# supply.net
KiCad netlist of a schematic drawn in EAGLE
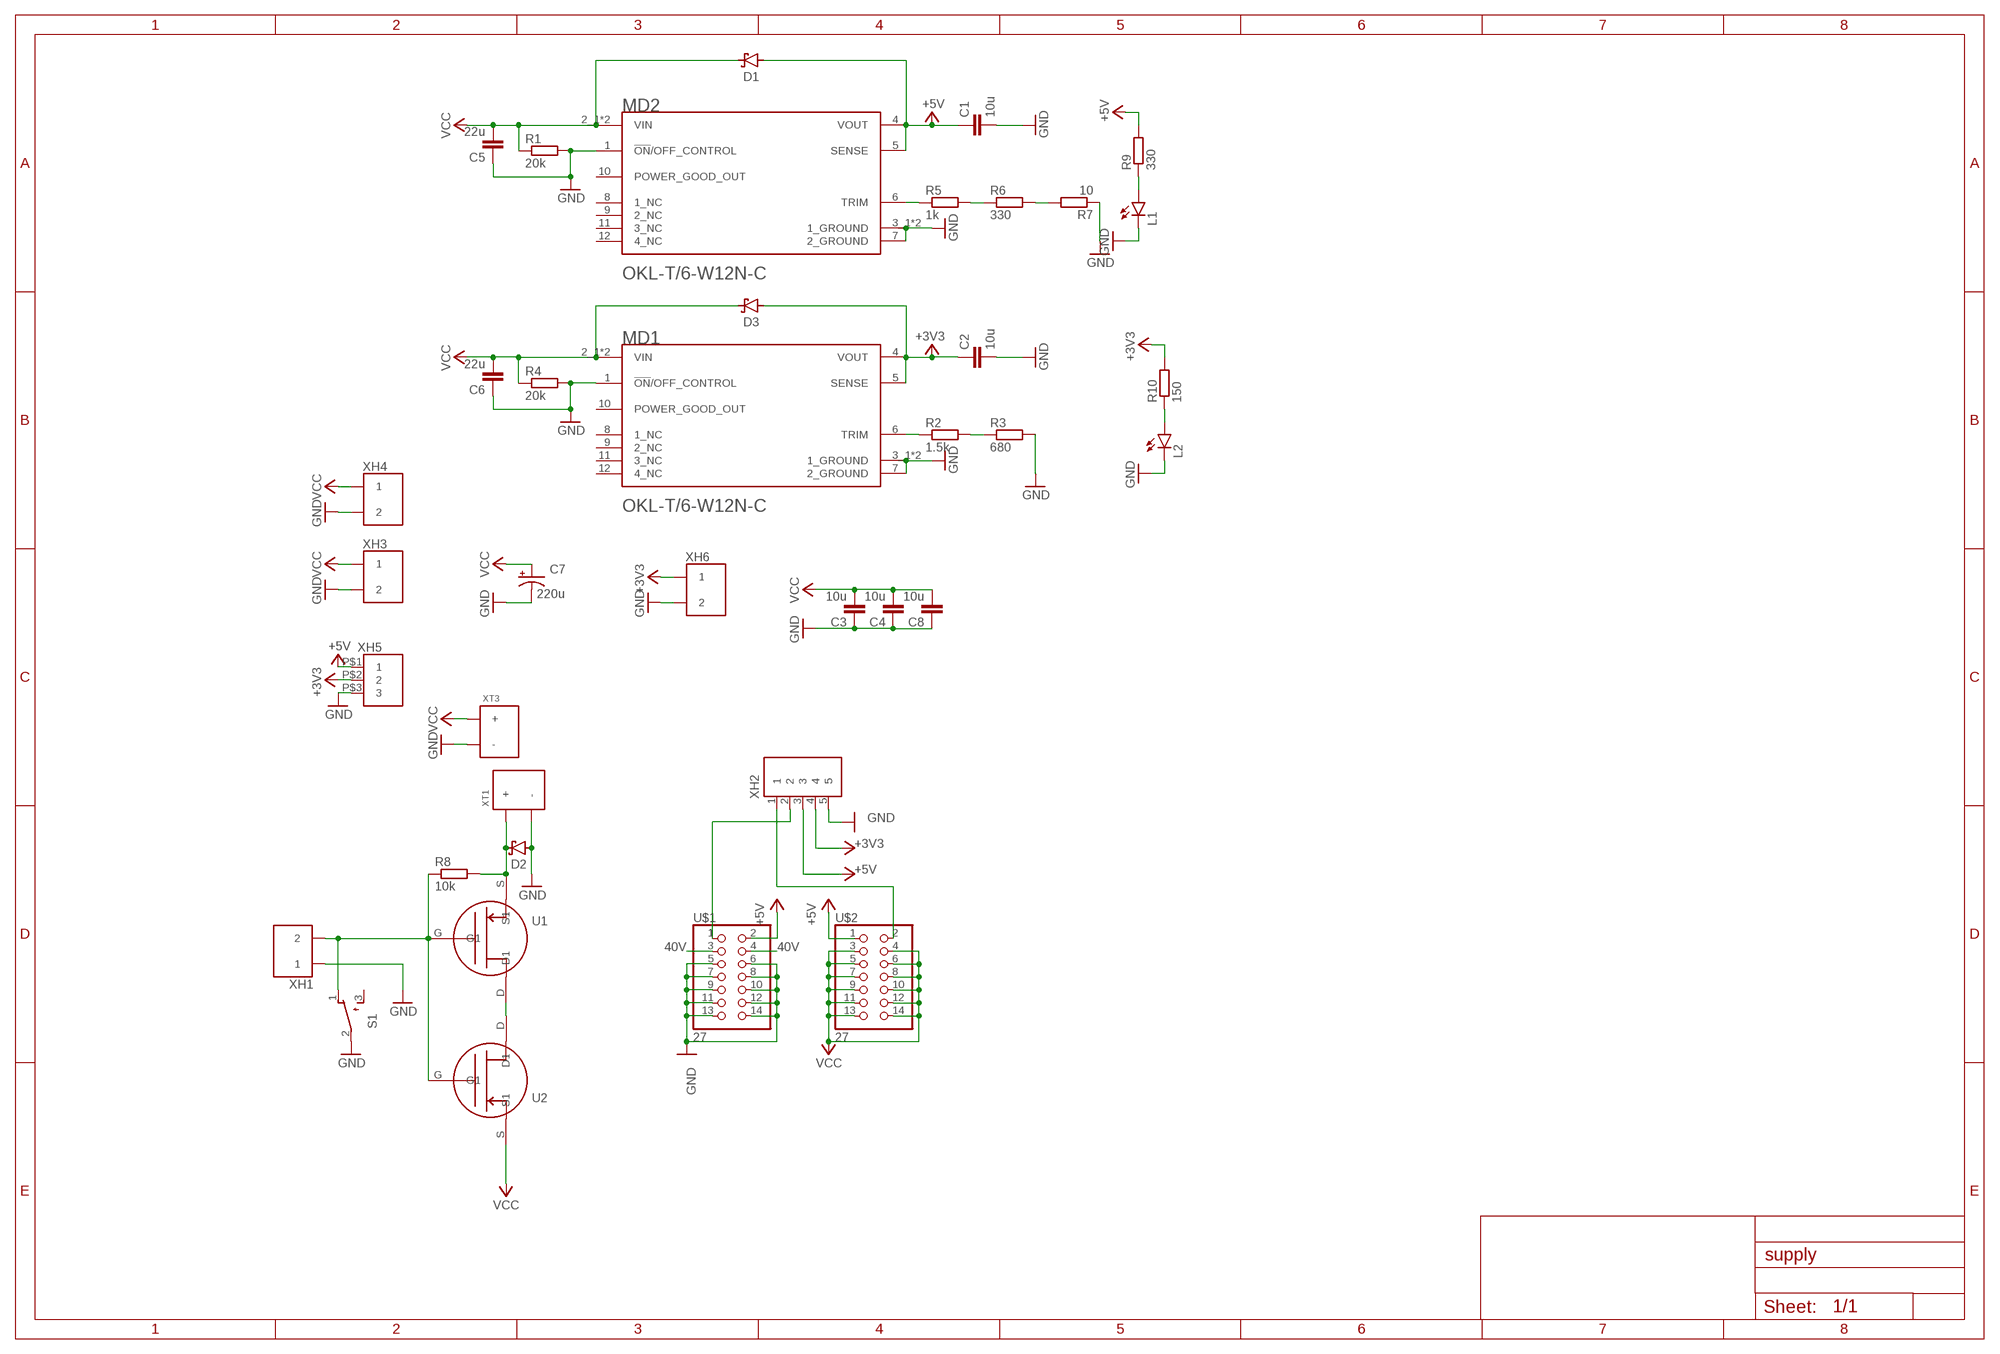
[diagram p0: schematic, sheet 1]

(export (version "E")
  (design (tool "Eeschema 10.0.6"))
  (components
    (comp (ref "C1")
      (value "10u")
      (footprint "eagle-import:C0805")
      (libsource (lib "eagle-import") (part "C-EUC0805"))
    )
    (comp (ref "C2")
      (value "10u")
      (footprint "eagle-import:C0805")
      (libsource (lib "eagle-import") (part "C-EUC0805"))
    )
    (comp (ref "C3")
      (value "10u")
      (footprint "eagle-import:C0805")
      (libsource (lib "eagle-import") (part "C-EUC0805"))
    )
    (comp (ref "C4")
      (value "10u")
      (footprint "eagle-import:C0805")
      (libsource (lib "eagle-import") (part "C-EUC0805"))
    )
    (comp (ref "C5")
      (value "22u")
      (footprint "eagle-import:C0805")
      (libsource (lib "eagle-import") (part "C-EUC0805"))
    )
    (comp (ref "C6")
      (value "22u")
      (footprint "eagle-import:C0805")
      (libsource (lib "eagle-import") (part "C-EUC0805"))
    )
    (comp (ref "C7")
      (value "220u")
      (footprint "eagle-import:CAPAE830X1080N")
      (libsource (lib "eagle-import") (part "UWT1E221MNL1GS"))
    )
    (comp (ref "C8")
      (value "10u")
      (footprint "eagle-import:C0805")
      (libsource (lib "eagle-import") (part "C-EUC0805"))
    )
    (comp (ref "D1")
      (value "SS2040FL")
      (footprint "eagle-import:SOD123FL")
      (libsource (lib "eagle-import") (part "SS2040FL"))
    )
    (comp (ref "D2")
      (value "SS2040FL")
      (footprint "eagle-import:SOD123FL")
      (libsource (lib "eagle-import") (part "SS2040FL"))
    )
    (comp (ref "D3")
      (value "SS2040FL")
      (footprint "eagle-import:SOD123FL")
      (libsource (lib "eagle-import") (part "SS2040FL"))
    )
    (comp (ref "L1")
      (value "SML-E12P8WT86")
      (footprint "eagle-import:LED_SML-LXFM0603SIC-TR")
      (libsource (lib "eagle-import") (part "SML-E12P8WT86"))
    )
    (comp (ref "L2")
      (value "SML-E12P8WT86")
      (footprint "eagle-import:LED_SML-LXFM0603SIC-TR")
      (libsource (lib "eagle-import") (part "SML-E12P8WT86"))
    )
    (comp (ref "MD1")
      (value "OKL-T/6-W12N-CMURATA_OKL-T-6-W12N-C_0_0")
      (footprint "eagle-import:MURATA_OKL-T-6-W12N-C_0")
      (fields (field (name "MF") "Murata Power Solutions Inc.") (field (name "MP") "OKL-T/6-W12N-C"))
      (libsource (lib "eagle-import") (part "OKL-T/6-W12N-CMURATA_OKL-T-6-W12N-C_0_0"))
    )
    (comp (ref "MD2")
      (value "OKL-T/6-W12N-CMURATA_OKL-T-6-W12N-C_0_0")
      (footprint "eagle-import:MURATA_OKL-T-6-W12N-C_0")
      (fields (field (name "MF") "Murata Power Solutions Inc.") (field (name "MP") "OKL-T/6-W12N-C"))
      (libsource (lib "eagle-import") (part "OKL-T/6-W12N-CMURATA_OKL-T-6-W12N-C_0_0"))
    )
    (comp (ref "R1")
      (value "20k")
      (footprint "eagle-import:R0603")
      (libsource (lib "eagle-import") (part "R-EU_R0603"))
    )
    (comp (ref "R2")
      (value "1.5k")
      (footprint "eagle-import:R0603")
      (libsource (lib "eagle-import") (part "R-EU_R0603"))
    )
    (comp (ref "R3")
      (value "680")
      (footprint "eagle-import:R0603")
      (libsource (lib "eagle-import") (part "R-EU_R0603"))
    )
    (comp (ref "R4")
      (value "20k")
      (footprint "eagle-import:R0603")
      (libsource (lib "eagle-import") (part "R-EU_R0603"))
    )
    (comp (ref "R5")
      (value "1k")
      (footprint "eagle-import:R0603")
      (libsource (lib "eagle-import") (part "R-EU_R0603"))
    )
    (comp (ref "R6")
      (value "330")
      (footprint "eagle-import:R0603")
      (libsource (lib "eagle-import") (part "R-EU_R0603"))
    )
    (comp (ref "R7")
      (value "10")
      (footprint "eagle-import:R0603")
      (libsource (lib "eagle-import") (part "R-EU_R0603"))
    )
    (comp (ref "R8")
      (value "10k")
      (footprint "eagle-import:R0603")
      (libsource (lib "eagle-import") (part "R-EU_R0603"))
    )
    (comp (ref "R9")
      (value "330")
      (footprint "eagle-import:R0603")
      (libsource (lib "eagle-import") (part "R-EU_R0603"))
    )
    (comp (ref "R10")
      (value "150")
      (footprint "eagle-import:R0603")
      (libsource (lib "eagle-import") (part "R-EU_R0603"))
    )
    (comp (ref "S1")
      (value "SS-12SDP2")
      (footprint "eagle-import:SS-12SDP2")
      (libsource (lib "eagle-import") (part "SS-12SDP2"))
    )
    (comp (ref "U$1")
      (value "27")
      (footprint "eagle-import:2_7")
      (libsource (lib "eagle-import") (part "27"))
    )
    (comp (ref "U$2")
      (value "27")
      (footprint "eagle-import:2_7")
      (libsource (lib "eagle-import") (part "27"))
    )
    (comp (ref "U1")
      (value "TJ60S04M3L")
      (footprint "eagle-import:DPACK")
      (libsource (lib "eagle-import") (part "TJ60S04M3L"))
    )
    (comp (ref "U2")
      (value "TJ60S04M3L")
      (footprint "eagle-import:DPACK")
      (libsource (lib "eagle-import") (part "TJ60S04M3L"))
    )
    (comp (ref "XH1") (value "2B") (footprint "eagle-import:2B") (libsource (lib "eagle-import") (part "2B")))
    (comp (ref "XH2") (value "5B") (footprint "eagle-import:5B") (libsource (lib "eagle-import") (part "5B")))
    (comp (ref "XH3") (value "2B") (footprint "eagle-import:2B") (libsource (lib "eagle-import") (part "2B")))
    (comp (ref "XH4") (value "2B") (footprint "eagle-import:2B") (libsource (lib "eagle-import") (part "2B")))
    (comp (ref "XH5") (value "3B") (footprint "eagle-import:3B") (libsource (lib "eagle-import") (part "3B")))
    (comp (ref "XH6") (value "2B") (footprint "eagle-import:2B") (libsource (lib "eagle-import") (part "2B")))
    (comp (ref "XT1")
      (value "XT60U-M")
      (footprint "eagle-import:XT60U-M")
      (libsource (lib "eagle-import") (part "XT60U-M"))
    )
    (comp (ref "XT3")
      (value "XT30U-M")
      (footprint "eagle-import:XT30U-M")
      (libsource (lib "eagle-import") (part "XT30U-M"))
    )
  )
  (nets
    (net (code "1") (name "+3V3") (class "Default")
      (node (ref "C2") (pin "1") (pinfunction "1_1") (pintype "passive"))
      (node (ref "D3") (pin "A") (pinfunction "A_A") (pintype "passive"))
      (node (ref "MD1") (pin "4") (pinfunction "VOUT_4") (pintype "bidirectional"))
      (node (ref "MD1") (pin "5") (pinfunction "SENSE_5") (pintype "passive"))
      (node (ref "R10") (pin "2") (pinfunction "2_2") (pintype "passive"))
      (node (ref "XH2") (pin "4") (pinfunction "4_4") (pintype "bidirectional"))
      (node (ref "XH5") (pin "P$2") (pinfunction "2_P$2") (pintype "bidirectional"))
      (node (ref "XH6") (pin "P$1") (pinfunction "1_P$1") (pintype "bidirectional"))
    )
    (net (code "2") (name "+5V") (class "Default")
      (node (ref "C1") (pin "1") (pinfunction "1_1") (pintype "passive"))
      (node (ref "D1") (pin "A") (pinfunction "A_A") (pintype "passive"))
      (node (ref "MD2") (pin "4") (pinfunction "VOUT_4") (pintype "bidirectional"))
      (node (ref "MD2") (pin "5") (pinfunction "SENSE_5") (pintype "passive"))
      (node (ref "R9") (pin "2") (pinfunction "2_2") (pintype "passive"))
      (node (ref "U$1") (pin "2") (pinfunction "2_2") (pintype "passive"))
      (node (ref "U$2") (pin "1") (pinfunction "1_1") (pintype "passive"))
      (node (ref "XH2") (pin "3") (pinfunction "3_3") (pintype "bidirectional"))
      (node (ref "XH5") (pin "P$1") (pinfunction "1_P$1") (pintype "bidirectional"))
    )
    (net (code "3") (name "/40V") (class "Default")
      (node (ref "U$1") (pin "3") (pinfunction "3_3") (pintype "passive"))
      (node (ref "U$1") (pin "4") (pinfunction "4_4") (pintype "passive"))
    )
    (net (code "4") (name "GND") (class "Default")
      (node (ref "C1") (pin "2") (pinfunction "2_2") (pintype "passive"))
      (node (ref "C2") (pin "2") (pinfunction "2_2") (pintype "passive"))
      (node (ref "C3") (pin "1") (pinfunction "1_1") (pintype "passive"))
      (node (ref "C4") (pin "1") (pinfunction "1_1") (pintype "passive"))
      (node (ref "C5") (pin "1") (pinfunction "1_1") (pintype "passive"))
      (node (ref "C6") (pin "1") (pinfunction "1_1") (pintype "passive"))
      (node (ref "C7") (pin "-") (pinfunction "-_-") (pintype "passive"))
      (node (ref "C8") (pin "1") (pinfunction "1_1") (pintype "passive"))
      (node (ref "D2") (pin "A") (pinfunction "A_A") (pintype "passive"))
      (node (ref "L1") (pin "C") (pinfunction "C_C") (pintype "passive"))
      (node (ref "L2") (pin "C") (pinfunction "C_C") (pintype "passive"))
      (node (ref "MD1") (pin "1") (pinfunction "~{ON}/OFF_CONTROL_1") (pintype "bidirectional"))
      (node (ref "MD1") (pin "3_1") (pinfunction "1_GROUND_3_1") (pintype "power_in"))
      (node (ref "MD1") (pin "3_2") (pinfunction "1_GROUND_3_2") (pintype "power_in"))
      (node (ref "MD1") (pin "7") (pinfunction "2_GROUND_7") (pintype "power_in"))
      (node (ref "MD2") (pin "1") (pinfunction "~{ON}/OFF_CONTROL_1") (pintype "bidirectional"))
      (node (ref "MD2") (pin "3_1") (pinfunction "1_GROUND_3_1") (pintype "power_in"))
      (node (ref "MD2") (pin "3_2") (pinfunction "1_GROUND_3_2") (pintype "power_in"))
      (node (ref "MD2") (pin "7") (pinfunction "2_GROUND_7") (pintype "power_in"))
      (node (ref "R1") (pin "2") (pinfunction "2_2") (pintype "passive"))
      (node (ref "R3") (pin "2") (pinfunction "2_2") (pintype "passive"))
      (node (ref "R4") (pin "2") (pinfunction "2_2") (pintype "passive"))
      (node (ref "R7") (pin "1") (pinfunction "1_1") (pintype "passive"))
      (node (ref "S1") (pin "2") (pinfunction "2_2") (pintype "passive"))
      (node (ref "U$1") (pin "10") (pinfunction "10_10") (pintype "passive"))
      (node (ref "U$1") (pin "11") (pinfunction "11_11") (pintype "passive"))
      (node (ref "U$1") (pin "12") (pinfunction "12_12") (pintype "passive"))
      (node (ref "U$1") (pin "13") (pinfunction "13_13") (pintype "passive"))
      (node (ref "U$1") (pin "14") (pinfunction "14_14") (pintype "passive"))
      (node (ref "U$1") (pin "5") (pinfunction "5_5") (pintype "passive"))
      (node (ref "U$1") (pin "6") (pinfunction "6_6") (pintype "passive"))
      (node (ref "U$1") (pin "7") (pinfunction "7_7") (pintype "passive"))
      (node (ref "U$1") (pin "8") (pinfunction "8_8") (pintype "passive"))
      (node (ref "U$1") (pin "9") (pinfunction "9_9") (pintype "passive"))
      (node (ref "XH1") (pin "P$1") (pinfunction "1_P$1") (pintype "bidirectional"))
      (node (ref "XH2") (pin "5") (pinfunction "5_5") (pintype "bidirectional"))
      (node (ref "XH3") (pin "P$2") (pinfunction "2_P$2") (pintype "bidirectional"))
      (node (ref "XH4") (pin "P$2") (pinfunction "2_P$2") (pintype "bidirectional"))
      (node (ref "XH5") (pin "P$3") (pinfunction "3_P$3") (pintype "bidirectional"))
      (node (ref "XH6") (pin "P$2") (pinfunction "2_P$2") (pintype "bidirectional"))
      (node (ref "XT1") (pin "-") (pinfunction "-_-") (pintype "bidirectional"))
      (node (ref "XT3") (pin "-") (pinfunction "-_-") (pintype "bidirectional"))
    )
    (net (code "5") (name "Net-(L1-PadA)") (class "Default")
      (node (ref "L1") (pin "A") (pinfunction "A_A") (pintype "passive"))
      (node (ref "R9") (pin "1") (pinfunction "1_1") (pintype "passive"))
    )
    (net (code "6") (name "Net-(L2-PadA)") (class "Default")
      (node (ref "L2") (pin "A") (pinfunction "A_A") (pintype "passive"))
      (node (ref "R10") (pin "1") (pinfunction "1_1") (pintype "passive"))
    )
    (net (code "7") (name "Net-(MD1-TRIM)") (class "Default")
      (node (ref "MD1") (pin "6") (pinfunction "TRIM_6") (pintype "passive"))
      (node (ref "R2") (pin "1") (pinfunction "1_1") (pintype "passive"))
    )
    (net (code "8") (name "Net-(MD2-TRIM)") (class "Default")
      (node (ref "MD2") (pin "6") (pinfunction "TRIM_6") (pintype "passive"))
      (node (ref "R5") (pin "1") (pinfunction "1_1") (pintype "passive"))
    )
    (net (code "9") (name "Net-(R2-Pad2)") (class "Default")
      (node (ref "R2") (pin "2") (pinfunction "2_2") (pintype "passive"))
      (node (ref "R3") (pin "1") (pinfunction "1_1") (pintype "passive"))
    )
    (net (code "10") (name "Net-(R5-Pad2)") (class "Default")
      (node (ref "R5") (pin "2") (pinfunction "2_2") (pintype "passive"))
      (node (ref "R6") (pin "1") (pinfunction "1_1") (pintype "passive"))
    )
    (net (code "11") (name "Net-(R6-Pad2)") (class "Default")
      (node (ref "R6") (pin "2") (pinfunction "2_2") (pintype "passive"))
      (node (ref "R7") (pin "2") (pinfunction "2_2") (pintype "passive"))
    )
    (net (code "12") (name "Net-(U$1-Pad1)") (class "Default")
      (node (ref "U$1") (pin "1") (pinfunction "1_1") (pintype "passive"))
      (node (ref "XH2") (pin "2") (pinfunction "2_2") (pintype "bidirectional"))
    )
    (net (code "13") (name "Net-(U$2-Pad2)") (class "Default")
      (node (ref "U$2") (pin "2") (pinfunction "2_2") (pintype "passive"))
      (node (ref "XH2") (pin "1") (pinfunction "1_1") (pintype "bidirectional"))
    )
    (net (code "14") (name "Net-(U1-D1)") (class "Default")
      (node (ref "U1") (pin "D") (pinfunction "D1_D") (pintype "bidirectional"))
      (node (ref "U2") (pin "D") (pinfunction "D1_D") (pintype "bidirectional"))
    )
    (net (code "15") (name "Net-(U1-G1)") (class "Default")
      (node (ref "R8") (pin "1") (pinfunction "1_1") (pintype "passive"))
      (node (ref "S1") (pin "1") (pinfunction "1_1") (pintype "passive"))
      (node (ref "U1") (pin "G") (pinfunction "G1_G") (pintype "bidirectional"))
      (node (ref "U2") (pin "G") (pinfunction "G1_G") (pintype "bidirectional"))
      (node (ref "XH1") (pin "P$2") (pinfunction "2_P$2") (pintype "bidirectional"))
    )
    (net (code "16") (name "Net-(U1-S1)") (class "Default")
      (node (ref "D2") (pin "C") (pinfunction "C_C") (pintype "passive"))
      (node (ref "R8") (pin "2") (pinfunction "2_2") (pintype "passive"))
      (node (ref "U1") (pin "S") (pinfunction "S1_S") (pintype "bidirectional"))
      (node (ref "XT1") (pin "+") (pinfunction "+_+") (pintype "bidirectional"))
    )
    (net (code "17") (name "VCC") (class "Default")
      (node (ref "C3") (pin "2") (pinfunction "2_2") (pintype "passive"))
      (node (ref "C4") (pin "2") (pinfunction "2_2") (pintype "passive"))
      (node (ref "C5") (pin "2") (pinfunction "2_2") (pintype "passive"))
      (node (ref "C6") (pin "2") (pinfunction "2_2") (pintype "passive"))
      (node (ref "C7") (pin "+") (pinfunction "+_+") (pintype "passive"))
      (node (ref "C8") (pin "2") (pinfunction "2_2") (pintype "passive"))
      (node (ref "D1") (pin "C") (pinfunction "C_C") (pintype "passive"))
      (node (ref "D3") (pin "C") (pinfunction "C_C") (pintype "passive"))
      (node (ref "MD1") (pin "2_1") (pinfunction "VIN_2_1") (pintype "bidirectional"))
      (node (ref "MD1") (pin "2_2") (pinfunction "VIN_2_2") (pintype "bidirectional"))
      (node (ref "MD2") (pin "2_1") (pinfunction "VIN_2_1") (pintype "bidirectional"))
      (node (ref "MD2") (pin "2_2") (pinfunction "VIN_2_2") (pintype "bidirectional"))
      (node (ref "R1") (pin "1") (pinfunction "1_1") (pintype "passive"))
      (node (ref "R4") (pin "1") (pinfunction "1_1") (pintype "passive"))
      (node (ref "U$2") (pin "10") (pinfunction "10_10") (pintype "passive"))
      (node (ref "U$2") (pin "11") (pinfunction "11_11") (pintype "passive"))
      (node (ref "U$2") (pin "12") (pinfunction "12_12") (pintype "passive"))
      (node (ref "U$2") (pin "13") (pinfunction "13_13") (pintype "passive"))
      (node (ref "U$2") (pin "14") (pinfunction "14_14") (pintype "passive"))
      (node (ref "U$2") (pin "3") (pinfunction "3_3") (pintype "passive"))
      (node (ref "U$2") (pin "4") (pinfunction "4_4") (pintype "passive"))
      (node (ref "U$2") (pin "5") (pinfunction "5_5") (pintype "passive"))
      (node (ref "U$2") (pin "6") (pinfunction "6_6") (pintype "passive"))
      (node (ref "U$2") (pin "7") (pinfunction "7_7") (pintype "passive"))
      (node (ref "U$2") (pin "8") (pinfunction "8_8") (pintype "passive"))
      (node (ref "U$2") (pin "9") (pinfunction "9_9") (pintype "passive"))
      (node (ref "U2") (pin "S") (pinfunction "S1_S") (pintype "bidirectional"))
      (node (ref "XH3") (pin "P$1") (pinfunction "1_P$1") (pintype "bidirectional"))
      (node (ref "XH4") (pin "P$1") (pinfunction "1_P$1") (pintype "bidirectional"))
      (node (ref "XT3") (pin "+") (pinfunction "+_+") (pintype "bidirectional"))
    )
    (net (code "18") (name "unconnected-(MD1-1_NC-Pad8)") (class "Default")
      (node (ref "MD1") (pin "8") (pinfunction "1_NC_8") (pintype "passive"))
    )
    (net (code "19") (name "unconnected-(MD1-2_NC-Pad9)") (class "Default")
      (node (ref "MD1") (pin "9") (pinfunction "2_NC_9") (pintype "passive"))
    )
    (net (code "20") (name "unconnected-(MD1-3_NC-Pad11)") (class "Default")
      (node (ref "MD1") (pin "11") (pinfunction "3_NC_11") (pintype "passive"))
    )
    (net (code "21") (name "unconnected-(MD1-4_NC-Pad12)") (class "Default")
      (node (ref "MD1") (pin "12") (pinfunction "4_NC_12") (pintype "passive"))
    )
    (net (code "22") (name "unconnected-(MD1-POWER_GOOD_OUT-Pad10)") (class "Default")
      (node (ref "MD1") (pin "10") (pinfunction "POWER_GOOD_OUT_10") (pintype "open_collector"))
    )
    (net (code "23") (name "unconnected-(MD2-1_NC-Pad8)") (class "Default")
      (node (ref "MD2") (pin "8") (pinfunction "1_NC_8") (pintype "passive"))
    )
    (net (code "24") (name "unconnected-(MD2-2_NC-Pad9)") (class "Default")
      (node (ref "MD2") (pin "9") (pinfunction "2_NC_9") (pintype "passive"))
    )
    (net (code "25") (name "unconnected-(MD2-3_NC-Pad11)") (class "Default")
      (node (ref "MD2") (pin "11") (pinfunction "3_NC_11") (pintype "passive"))
    )
    (net (code "26") (name "unconnected-(MD2-4_NC-Pad12)") (class "Default")
      (node (ref "MD2") (pin "12") (pinfunction "4_NC_12") (pintype "passive"))
    )
    (net (code "27") (name "unconnected-(MD2-POWER_GOOD_OUT-Pad10)") (class "Default")
      (node (ref "MD2") (pin "10") (pinfunction "POWER_GOOD_OUT_10") (pintype "open_collector"))
    )
    (net (code "28") (name "unconnected-(S1-Pad3)") (class "Default")
      (node (ref "S1") (pin "3") (pinfunction "3_3") (pintype "passive"))
    )
  )
)
